# Li-Ion_Batteryy.net
KiCad netlist of a schematic drawn in EAGLE
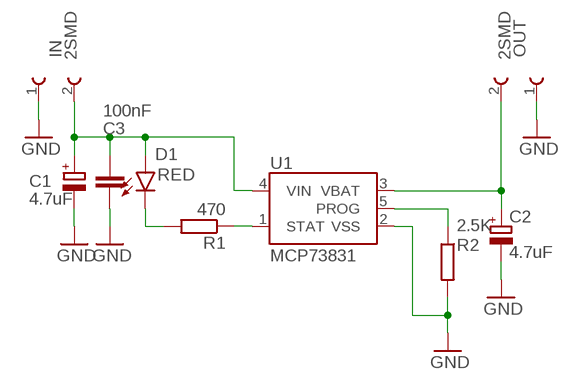
[diagram p0: schematic, sheet 1]

(export (version "E")
  (design (tool "Eeschema 10.0.6"))
  (components
    (comp (ref "C1")
      (value "4.7uF")
      (footprint "eagle-import:SMC_A")
      (libsource (lib "eagle-import") (part "CPOL-EUSMCA"))
    )
    (comp (ref "C2")
      (value "4.7uF")
      (footprint "eagle-import:SMC_A")
      (libsource (lib "eagle-import") (part "CPOL-EUSMCA"))
    )
    (comp (ref "C3")
      (value "100nF")
      (footprint "eagle-import:C0805")
      (libsource (lib "eagle-import") (part "C-EUC0805"))
    )
    (comp (ref "D1")
      (value "RED")
      (footprint "eagle-import:LED-1206")
      (libsource (lib "eagle-import") (part "LED-RED1206"))
    )
    (comp (ref "IN")
      (value "2SMD")
      (footprint "eagle-import:2SMD")
      (libsource (lib "eagle-import") (part "2SMD"))
    )
    (comp (ref "OUT")
      (value "2SMD")
      (footprint "eagle-import:2SMD")
      (libsource (lib "eagle-import") (part "2SMD"))
    )
    (comp (ref "R1")
      (value "470")
      (footprint "eagle-import:R1206")
      (libsource (lib "eagle-import") (part "R-EU_R1206"))
    )
    (comp (ref "R2")
      (value "2.5K")
      (footprint "eagle-import:R1206")
      (libsource (lib "eagle-import") (part "R-EU_R1206"))
    )
    (comp (ref "U1")
      (value "MCP73831")
      (footprint "eagle-import:SOT23-5")
      (libsource (lib "eagle-import") (part "MCP73831"))
    )
  )
  (nets
    (net (code "1") (name "GND") (class "Default")
      (node (ref "C1") (pin "-") (pinfunction "-_-") (pintype "passive"))
      (node (ref "C2") (pin "-") (pinfunction "-_-") (pintype "passive"))
      (node (ref "C3") (pin "2") (pinfunction "2_2") (pintype "passive"))
      (node (ref "IN") (pin "1") (pinfunction "1_1") (pintype "passive"))
      (node (ref "OUT") (pin "1") (pinfunction "1_1") (pintype "passive"))
      (node (ref "R2") (pin "2") (pinfunction "2_2") (pintype "passive"))
      (node (ref "U1") (pin "2") (pinfunction "VSS_2") (pintype "power_in"))
    )
    (net (code "2") (name "Net-(D1-PadC)") (class "Default")
      (node (ref "D1") (pin "C") (pinfunction "C_C") (pintype "passive"))
      (node (ref "R1") (pin "2") (pinfunction "2_2") (pintype "passive"))
    )
    (net (code "3") (name "Net-(U1-PROG)") (class "Default")
      (node (ref "R2") (pin "1") (pinfunction "1_1") (pintype "passive"))
      (node (ref "U1") (pin "5") (pinfunction "PROG_5") (pintype "input"))
    )
    (net (code "4") (name "Net-(U1-STAT)") (class "Default")
      (node (ref "R1") (pin "1") (pinfunction "1_1") (pintype "passive"))
      (node (ref "U1") (pin "1") (pinfunction "STAT_1") (pintype "output"))
    )
    (net (code "5") (name "Net-(U1-VBAT)") (class "Default")
      (node (ref "C2") (pin "+") (pinfunction "+_+") (pintype "passive"))
      (node (ref "OUT") (pin "2") (pinfunction "2_2") (pintype "passive"))
      (node (ref "U1") (pin "3") (pinfunction "VBAT_3") (pintype "power_in"))
    )
    (net (code "6") (name "Net-(U1-VIN)") (class "Default")
      (node (ref "C1") (pin "+") (pinfunction "+_+") (pintype "passive"))
      (node (ref "C3") (pin "1") (pinfunction "1_1") (pintype "passive"))
      (node (ref "D1") (pin "A") (pinfunction "A_A") (pintype "passive"))
      (node (ref "IN") (pin "2") (pinfunction "2_2") (pintype "passive"))
      (node (ref "U1") (pin "4") (pinfunction "VIN_4") (pintype "power_in"))
    )
  )
)
